# lab2_demcheva_buck.net
KiCad netlist of a schematic drawn in Altium Designer
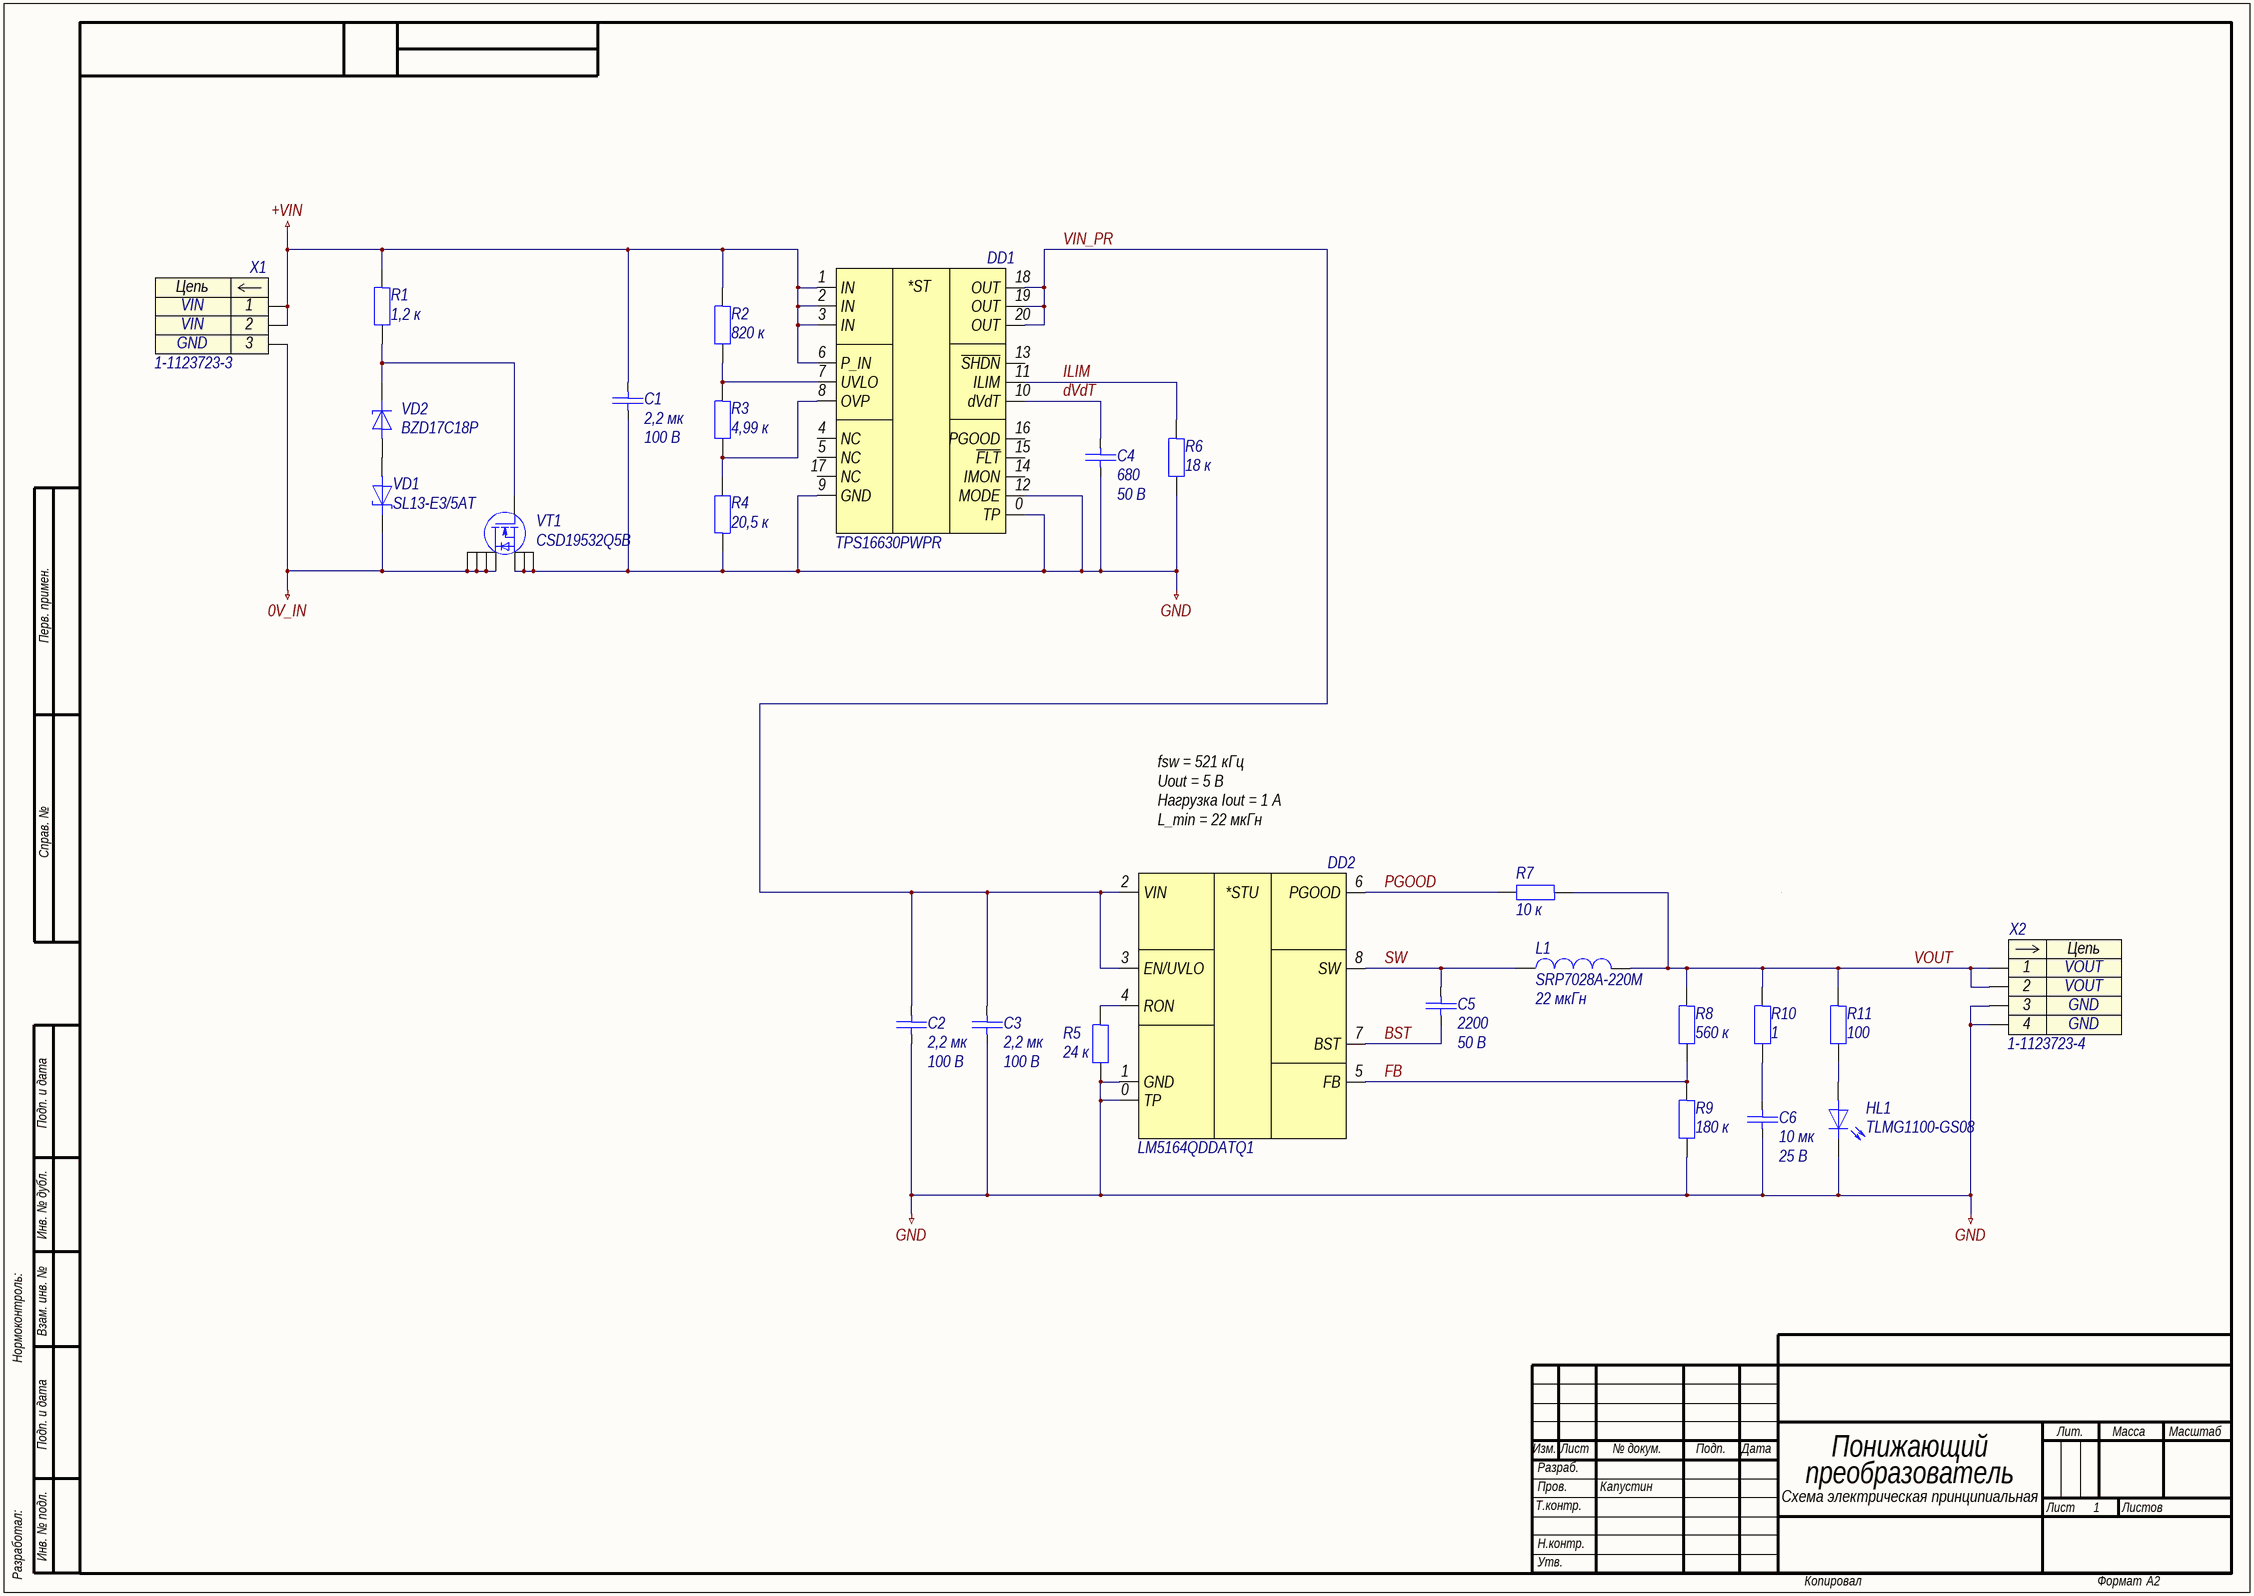
[diagram p0: lab2_demcheva_buck.SchDoc]

(export (version "E")
  (design (tool "Eeschema 10.0.6"))
  (components
    (comp (ref "C1")
      (value "2,2 мк")
      (footprint "C1206")
      (description "=Описание")
      (fields (field (name "НАПРЯЖЕНИЕ") "100 В"))
      (libsource (lib "Database_Students") (part "C-NONPOLAR"))
    )
    (comp (ref "C2")
      (value "2,2 мк")
      (footprint "C1206")
      (description "=Описание")
      (fields (field (name "НАПРЯЖЕНИЕ") "100 В"))
      (libsource (lib "Database_Students") (part "C-NONPOLAR"))
    )
    (comp (ref "C3")
      (value "2,2 мк")
      (footprint "C1206")
      (description "=Описание")
      (fields (field (name "НАПРЯЖЕНИЕ") "100 В"))
      (libsource (lib "Database_Students") (part "C-NONPOLAR"))
    )
    (comp (ref "C4")
      (value "680")
      (footprint "C0603")
      (description "=Описание")
      (fields (field (name "НАПРЯЖЕНИЕ") "50 В"))
      (libsource (lib "Database_Students") (part "C-NONPOLAR"))
    )
    (comp (ref "C5")
      (value "2200")
      (footprint "C0603")
      (description "=Описание")
      (fields (field (name "НАПРЯЖЕНИЕ") "50 В"))
      (libsource (lib "Database_Students") (part "C-NONPOLAR"))
    )
    (comp (ref "C6")
      (value "10 мк")
      (footprint "C1206")
      (description "=Описание")
      (fields (field (name "НАПРЯЖЕНИЕ") "25 В"))
      (libsource (lib "Database_Students") (part "C-NONPOLAR"))
    )
    (comp (ref "DD1")
      (value "TPS16630PWPR")
      (footprint "HTSSOP-20")
      (description "=Описание")
      (libsource (lib "Database_Students") (part "TPS16630PWPR"))
    )
    (comp (ref "DD2")
      (value "LM5164QDDATQ1")
      (footprint "HSOIC-8")
      (description "=Описание")
      (libsource (lib "Database_Students") (part "LM5164QDDATQ1"))
    )
    (comp (ref "HL1")
      (value "TLMG1100-GS08")
      (footprint "HL0603")
      (description "=Описание")
      (libsource (lib "Database_Students") (part "HL-COMMON"))
    )
    (comp (ref "L1")
      (value "SRP7028A-220M")
      (footprint "SRP-2-670X660X280")
      (description "=Описание")
      (fields (field (name "ИНДУКТИВНОСТЬ") "22 мкГн"))
      (libsource (lib "Database_Students") (part "INDUCTOR-COMMON"))
    )
    (comp (ref "R1")
      (value "1,2 к")
      (footprint "R0603")
      (description "=Описание")
      (libsource (lib "Database_Students") (part "R-COMMON"))
    )
    (comp (ref "R2")
      (value "820 к")
      (footprint "R0603")
      (description "=Описание")
      (libsource (lib "Database_Students") (part "R-COMMON"))
    )
    (comp (ref "R3")
      (value "4,99 к")
      (footprint "R0603")
      (description "=Описание")
      (libsource (lib "Database_Students") (part "R-COMMON"))
    )
    (comp (ref "R4")
      (value "20,5 к")
      (footprint "R0603")
      (description "=Описание")
      (libsource (lib "Database_Students") (part "R-COMMON"))
    )
    (comp (ref "R5")
      (value "24 к")
      (footprint "R0603")
      (description "=Описание")
      (libsource (lib "Database_Students") (part "R-COMMON"))
    )
    (comp (ref "R6")
      (value "18 к")
      (footprint "R0603")
      (description "=Описание")
      (libsource (lib "Database_Students") (part "R-COMMON"))
    )
    (comp (ref "R7")
      (value "10 к")
      (footprint "R0603")
      (description "=Описание")
      (libsource (lib "Database_Students") (part "R-COMMON"))
    )
    (comp (ref "R8")
      (value "560 к")
      (footprint "R0603")
      (description "=Описание")
      (libsource (lib "Database_Students") (part "R-COMMON"))
    )
    (comp (ref "R9")
      (value "180 к")
      (footprint "R0603")
      (description "=Описание")
      (libsource (lib "Database_Students") (part "R-COMMON"))
    )
    (comp (ref "R10")
      (value "1")
      (footprint "R0603")
      (description "=Описание")
      (libsource (lib "Database_Students") (part "R-COMMON"))
    )
    (comp (ref "R11")
      (value "100")
      (footprint "R0603")
      (description "=Описание")
      (libsource (lib "Database_Students") (part "R-COMMON"))
    )
    (comp (ref "VD1")
      (value "SL13-E3/5AT")
      (footprint "DO-214AC")
      (description "=Описание")
      (libsource (lib "Database_Students") (part "DIODE-SCHOTTKY"))
    )
    (comp (ref "VD2")
      (value "BZD17C18P")
      (footprint "DO-219AB")
      (description "=Описание")
      (libsource (lib "Database_Students") (part "ZENER-DIODE"))
    )
    (comp (ref "VT1")
      (value "CSD19532Q5B")
      (footprint "SON-8")
      (description "=Описание")
      (libsource (lib "Database_Students") (part "MOSFET-3S-4D"))
    )
    (comp (ref "X1")
      (value "1-1123723-3")
      (footprint "1-1123723-3")
      (description "=Описание")
      (libsource (lib "Database_Students") (part "HEADER-3-PLG"))
    )
    (comp (ref "X2")
      (value "1-1123723-4")
      (footprint "1-1123723-4")
      (description "=Описание")
      (libsource (lib "Database_Students") (part "HEADER-4-PLG"))
    )
  )
  (nets
    (net (code "1") (name "+VIN") (class "Default")
      (node (ref "C1") (pin "2") (pinfunction "2_2") (pintype "passive"))
      (node (ref "DD1") (pin "1") (pinfunction "IN_1") (pintype "passive"))
      (node (ref "DD1") (pin "2") (pinfunction "IN_2") (pintype "passive"))
      (node (ref "DD1") (pin "3") (pinfunction "IN_3") (pintype "passive"))
      (node (ref "DD1") (pin "6") (pinfunction "P_IN_6") (pintype "passive"))
      (node (ref "R1") (pin "1") (pinfunction "1_1") (pintype "passive"))
      (node (ref "R2") (pin "1") (pinfunction "1_1") (pintype "passive"))
      (node (ref "X1") (pin "1") (pinfunction "1_1") (pintype "passive"))
      (node (ref "X1") (pin "2") (pinfunction "2_2") (pintype "passive"))
    )
    (net (code "2") (name "/BST") (class "Default")
      (node (ref "C5") (pin "1") (pinfunction "1_1") (pintype "passive"))
      (node (ref "DD2") (pin "7") (pinfunction "BST_7") (pintype "passive"))
    )
    (net (code "3") (name "/FB") (class "Default")
      (node (ref "DD2") (pin "5") (pinfunction "FB_5") (pintype "passive"))
      (node (ref "R8") (pin "2") (pinfunction "2_2") (pintype "passive"))
      (node (ref "R9") (pin "1") (pinfunction "1_1") (pintype "passive"))
    )
    (net (code "4") (name "/ILIM") (class "Default")
      (node (ref "DD1") (pin "11") (pinfunction "ILIM_11") (pintype "passive"))
      (node (ref "R6") (pin "1") (pinfunction "1_1") (pintype "passive"))
    )
    (net (code "5") (name "/PGOOD") (class "Default")
      (node (ref "DD2") (pin "6") (pinfunction "PGOOD_6") (pintype "passive"))
      (node (ref "R7") (pin "2") (pinfunction "2_2") (pintype "passive"))
    )
    (net (code "6") (name "/SW") (class "Default")
      (node (ref "C5") (pin "2") (pinfunction "2_2") (pintype "passive"))
      (node (ref "DD2") (pin "8") (pinfunction "SW_8") (pintype "passive"))
      (node (ref "L1") (pin "1") (pinfunction "1_1") (pintype "passive"))
    )
    (net (code "7") (name "/VIN_PR") (class "Default")
      (node (ref "C2") (pin "2") (pinfunction "2_2") (pintype "passive"))
      (node (ref "C3") (pin "2") (pinfunction "2_2") (pintype "passive"))
      (node (ref "DD1") (pin "18") (pinfunction "OUT_18") (pintype "passive"))
      (node (ref "DD1") (pin "19") (pinfunction "OUT_19") (pintype "passive"))
      (node (ref "DD1") (pin "20") (pinfunction "OUT_20") (pintype "passive"))
      (node (ref "DD2") (pin "2") (pinfunction "VIN_2") (pintype "passive"))
      (node (ref "DD2") (pin "3") (pinfunction "EN/UVLO_3") (pintype "passive"))
    )
    (net (code "8") (name "/VOUT") (class "Default")
      (node (ref "L1") (pin "2") (pinfunction "2_2") (pintype "passive"))
      (node (ref "R10") (pin "1") (pinfunction "1_1") (pintype "passive"))
      (node (ref "R11") (pin "1") (pinfunction "1_1") (pintype "passive"))
      (node (ref "R7") (pin "1") (pinfunction "1_1") (pintype "passive"))
      (node (ref "R8") (pin "1") (pinfunction "1_1") (pintype "passive"))
      (node (ref "X2") (pin "1") (pinfunction "1_1") (pintype "passive"))
      (node (ref "X2") (pin "2") (pinfunction "2_2") (pintype "passive"))
    )
    (net (code "9") (name "/dVdT") (class "Default")
      (node (ref "C4") (pin "2") (pinfunction "2_2") (pintype "passive"))
      (node (ref "DD1") (pin "10") (pinfunction "dVdT_10") (pintype "passive"))
    )
    (net (code "10") (name "0V_IN") (class "Default")
      (node (ref "VD1") (pin "1") (pinfunction "1_1") (pintype "passive"))
      (node (ref "VT1") (pin "D") (pinfunction "D_D") (pintype "passive"))
      (node (ref "X1") (pin "3") (pinfunction "3_3") (pintype "passive"))
    )
    (net (code "11") (name "GND") (class "Default")
      (node (ref "C1") (pin "1") (pinfunction "1_1") (pintype "passive"))
      (node (ref "C2") (pin "1") (pinfunction "1_1") (pintype "passive"))
      (node (ref "C3") (pin "1") (pinfunction "1_1") (pintype "passive"))
      (node (ref "C4") (pin "1") (pinfunction "1_1") (pintype "passive"))
      (node (ref "C6") (pin "1") (pinfunction "1_1") (pintype "passive"))
      (node (ref "DD1") (pin "0") (pinfunction "TP_0") (pintype "passive"))
      (node (ref "DD1") (pin "12") (pinfunction "MODE_12") (pintype "passive"))
      (node (ref "DD1") (pin "9") (pinfunction "GND_9") (pintype "passive"))
      (node (ref "DD2") (pin "0") (pinfunction "TP_0") (pintype "passive"))
      (node (ref "DD2") (pin "1") (pinfunction "GND_1") (pintype "passive"))
      (node (ref "HL1") (pin "1") (pinfunction "1_1") (pintype "passive"))
      (node (ref "R4") (pin "1") (pinfunction "1_1") (pintype "passive"))
      (node (ref "R5") (pin "2") (pinfunction "2_2") (pintype "passive"))
      (node (ref "R6") (pin "2") (pinfunction "2_2") (pintype "passive"))
      (node (ref "R9") (pin "2") (pinfunction "2_2") (pintype "passive"))
      (node (ref "VT1") (pin "S") (pinfunction "S_S") (pintype "passive"))
      (node (ref "X2") (pin "3") (pinfunction "3_3") (pintype "passive"))
      (node (ref "X2") (pin "4") (pinfunction "4_4") (pintype "passive"))
    )
    (net (code "12") (name "Net-(C6-Pad2)") (class "Default")
      (node (ref "C6") (pin "2") (pinfunction "2_2") (pintype "passive"))
      (node (ref "R10") (pin "2") (pinfunction "2_2") (pintype "passive"))
    )
    (net (code "13") (name "Net-(DD1-OVP)") (class "Default")
      (node (ref "DD1") (pin "8") (pinfunction "OVP_8") (pintype "passive"))
      (node (ref "R3") (pin "2") (pinfunction "2_2") (pintype "passive"))
      (node (ref "R4") (pin "2") (pinfunction "2_2") (pintype "passive"))
    )
    (net (code "14") (name "Net-(DD1-UVLO)") (class "Default")
      (node (ref "DD1") (pin "7") (pinfunction "UVLO_7") (pintype "passive"))
      (node (ref "R2") (pin "2") (pinfunction "2_2") (pintype "passive"))
      (node (ref "R3") (pin "1") (pinfunction "1_1") (pintype "passive"))
    )
    (net (code "15") (name "Net-(DD2-RON)") (class "Default")
      (node (ref "DD2") (pin "4") (pinfunction "RON_4") (pintype "passive"))
      (node (ref "R5") (pin "1") (pinfunction "1_1") (pintype "passive"))
    )
    (net (code "16") (name "Net-(HL1-Pad2)") (class "Default")
      (node (ref "HL1") (pin "2") (pinfunction "2_2") (pintype "passive"))
      (node (ref "R11") (pin "2") (pinfunction "2_2") (pintype "passive"))
    )
    (net (code "17") (name "Net-(R1-Pad2)") (class "Default")
      (node (ref "R1") (pin "2") (pinfunction "2_2") (pintype "passive"))
      (node (ref "VD2") (pin "1") (pinfunction "1_1") (pintype "passive"))
      (node (ref "VT1") (pin "G") (pinfunction "G_G") (pintype "passive"))
    )
    (net (code "18") (name "Net-(VD1-Pad2)") (class "Default")
      (node (ref "VD1") (pin "2") (pinfunction "2_2") (pintype "passive"))
      (node (ref "VD2") (pin "2") (pinfunction "2_2") (pintype "passive"))
    )
    (net (code "19") (name "unconnected-(DD1-IMON-Pad14)") (class "Default")
      (node (ref "DD1") (pin "14") (pinfunction "IMON_14") (pintype "passive"))
    )
    (net (code "20") (name "unconnected-(DD1-NC-Pad4)") (class "Default")
      (node (ref "DD1") (pin "4") (pinfunction "NC_4") (pintype "passive"))
    )
    (net (code "21") (name "unconnected-(DD1-NC-Pad5)") (class "Default")
      (node (ref "DD1") (pin "5") (pinfunction "NC_5") (pintype "passive"))
    )
    (net (code "22") (name "unconnected-(DD1-NC-Pad17)") (class "Default")
      (node (ref "DD1") (pin "17") (pinfunction "NC_17") (pintype "passive"))
    )
    (net (code "23") (name "unconnected-(DD1-PGOOD-Pad16)") (class "Default")
      (node (ref "DD1") (pin "16") (pinfunction "PGOOD_16") (pintype "passive"))
    )
    (net (code "24") (name "unconnected-(DD1-~{FLT}-Pad15)") (class "Default")
      (node (ref "DD1") (pin "15") (pinfunction "~{FLT}_15") (pintype "passive"))
    )
    (net (code "25") (name "unconnected-(DD1-~{SHDN}-Pad13)") (class "Default")
      (node (ref "DD1") (pin "13") (pinfunction "~{SHDN}_13") (pintype "passive"))
    )
  )
)
